# 06_-_Soft_DPHY.net
KiCad netlist of a schematic drawn in Altium Designer
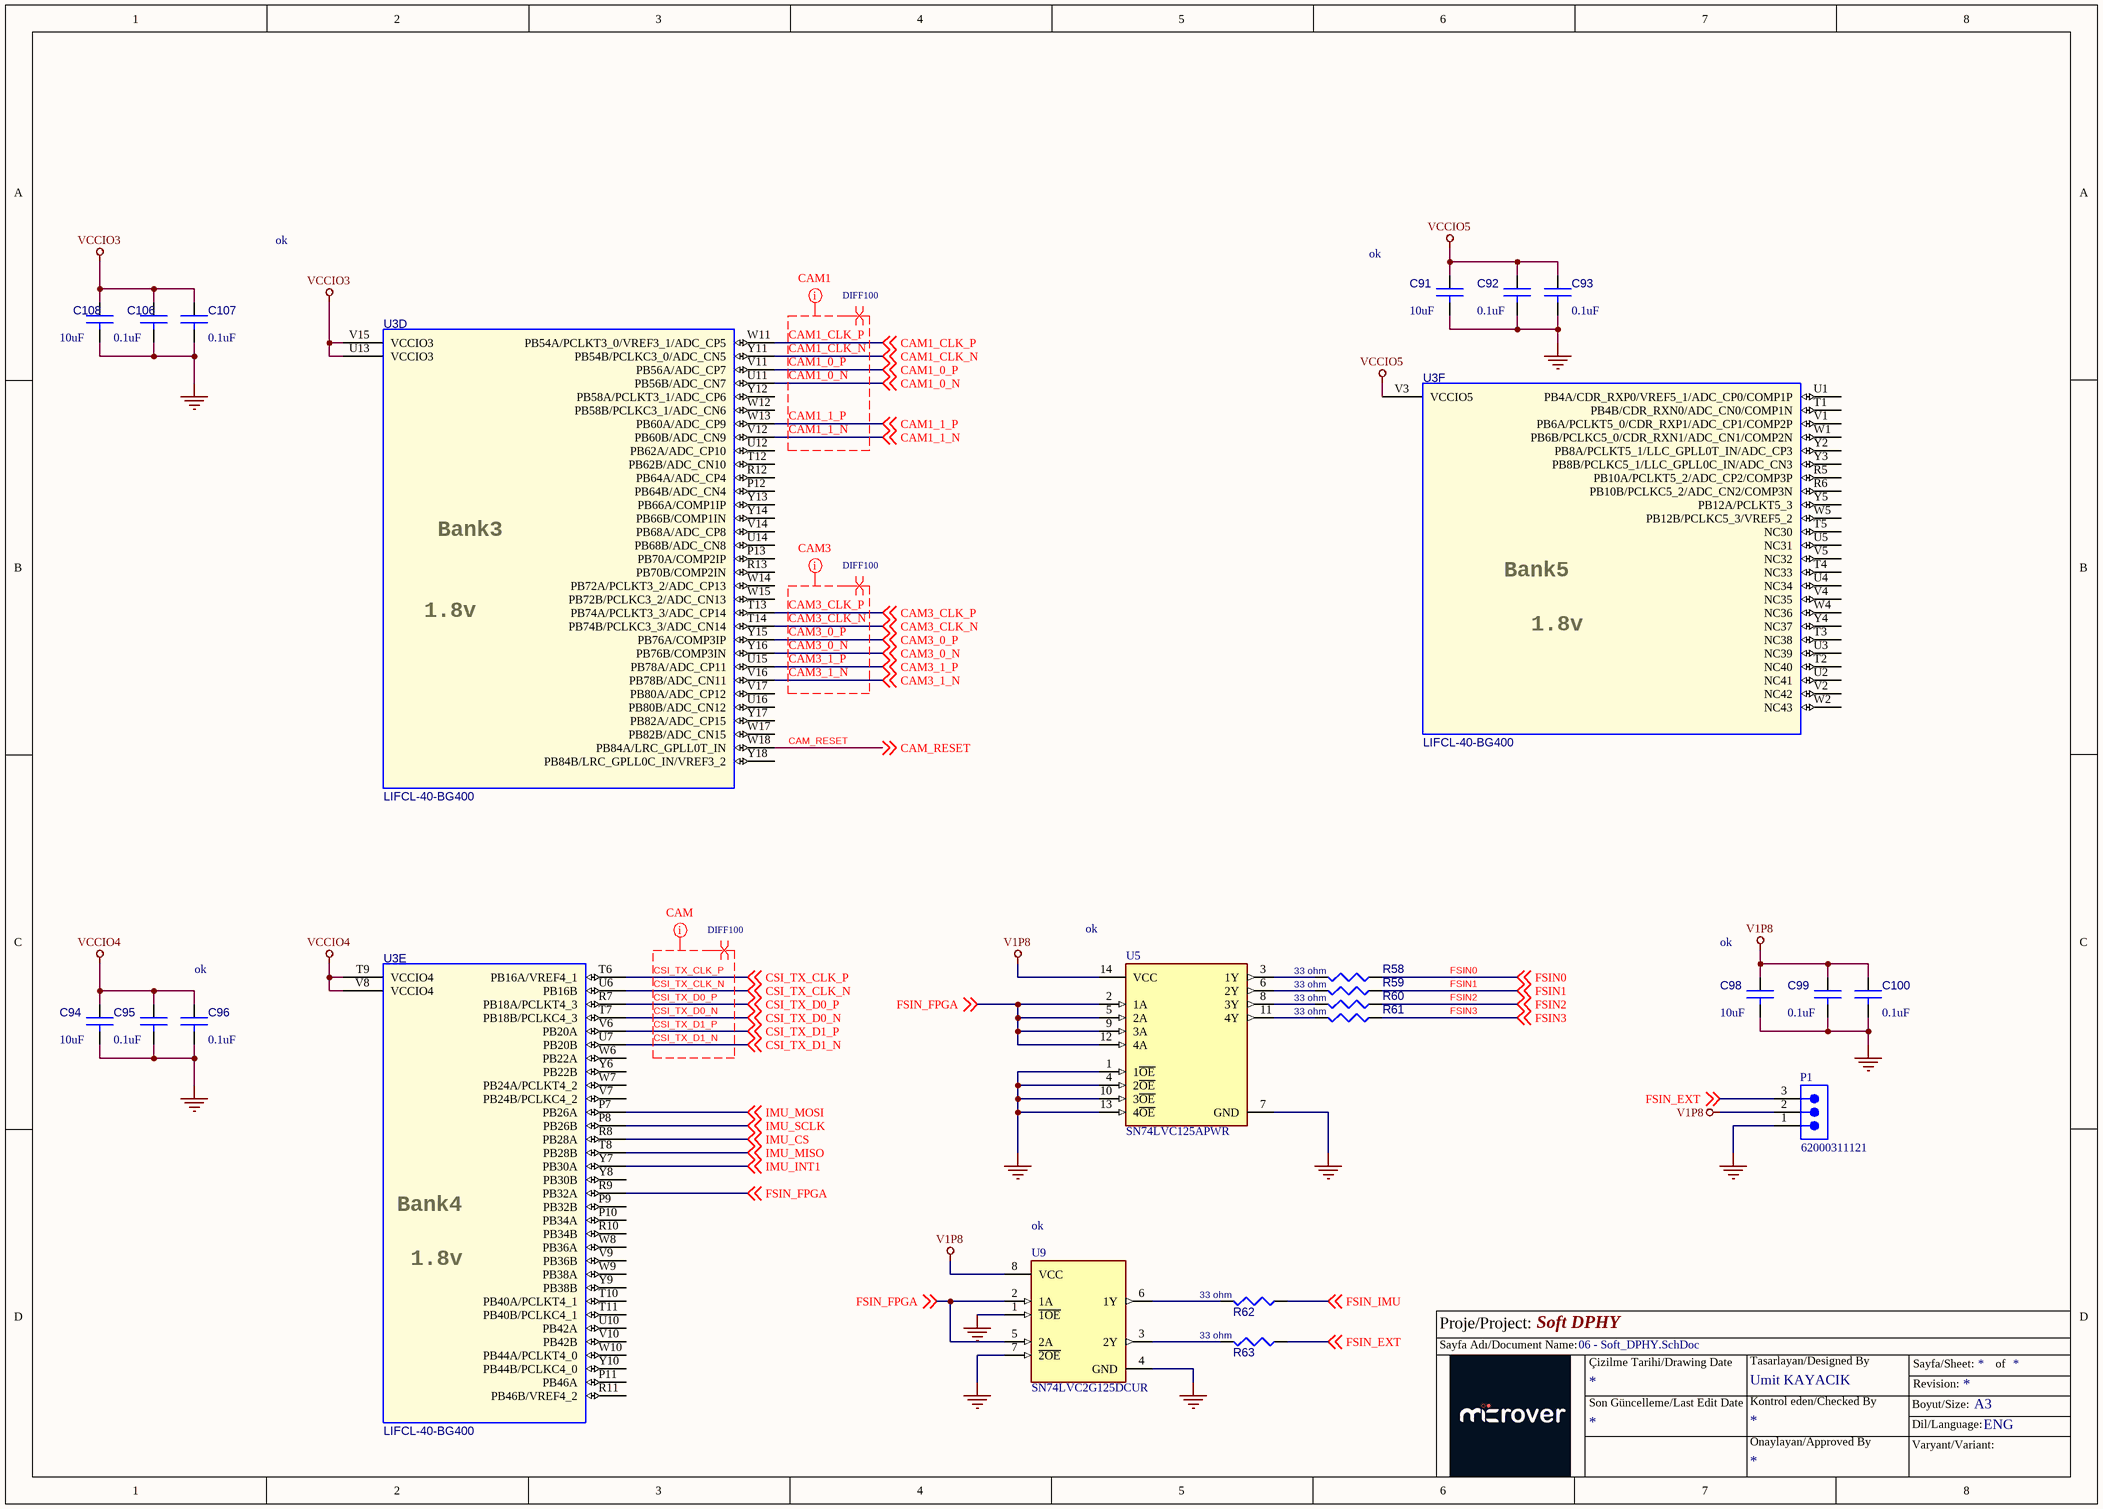
[diagram p0: 06 - Soft_DPHY.SchDoc]

(export (version "E")
  (design (tool "Eeschema 10.0.6"))
  (components
    (comp (ref "C91")
      (value "10uF")
      (footprint "C0603")
      (description "CAP CECAP CER 10UF 10V X5R 20% 0603")
      (fields
        (field (name "MANUFACTURER") "Taiyo Yuden")
        (field (name "MANUFACTURER PART NUMBER") "LMK107BJ106MALTD")
      )
      (libsource (lib "*") (part "10uF_0603"))
    )
    (comp (ref "C92")
      (value "0.1uF")
      (footprint "C0201")
      (description "CAP CER 0.1UF 25V 10% X5R 0201")
      (fields
        (field (name "MANUFACTURER") "Murata")
        (field (name "MANUFACTURER PART NUMBER") "GRM033R61E104KE14J")
      )
      (libsource (lib "*") (part "0u1_0402"))
    )
    (comp (ref "C93")
      (value "0.1uF")
      (footprint "C0201")
      (description "CAP CER 0.1UF 25V 10% X5R 0201")
      (fields
        (field (name "MANUFACTURER") "Murata")
        (field (name "MANUFACTURER PART NUMBER") "GRM033R61E104KE14J")
      )
      (libsource (lib "*") (part "0u1_0402"))
    )
    (comp (ref "C94")
      (value "10uF")
      (footprint "C0603")
      (description "CAP CECAP CER 10UF 10V X5R 20% 0603")
      (fields
        (field (name "MANUFACTURER") "Taiyo Yuden")
        (field (name "MANUFACTURER PART NUMBER") "LMK107BJ106MALTD")
      )
      (libsource (lib "*") (part "10uF_0603"))
    )
    (comp (ref "C95")
      (value "0.1uF")
      (footprint "C0201")
      (description "CAP CER 0.1UF 25V 10% X5R 0201")
      (fields
        (field (name "MANUFACTURER") "Murata")
        (field (name "MANUFACTURER PART NUMBER") "GRM033R61E104KE14J")
      )
      (libsource (lib "*") (part "0u1_0402"))
    )
    (comp (ref "C96")
      (value "0.1uF")
      (footprint "C0201")
      (description "CAP CER 0.1UF 25V 10% X5R 0201")
      (fields
        (field (name "MANUFACTURER") "Murata")
        (field (name "MANUFACTURER PART NUMBER") "GRM033R61E104KE14J")
      )
      (libsource (lib "*") (part "0u1_0402"))
    )
    (comp (ref "C98")
      (value "10uF")
      (footprint "C0603")
      (description "CAP CECAP CER 10UF 10V X5R 20% 0603")
      (fields
        (field (name "MANUFACTURER") "Taiyo Yuden")
        (field (name "MANUFACTURER PART NUMBER") "LMK107BJ106MALTD")
      )
      (libsource (lib "*") (part "10uF_0603"))
    )
    (comp (ref "C99")
      (value "0.1uF")
      (footprint "C0201")
      (description "CAP CER 0.1UF 25V 10% X5R 0201")
      (fields
        (field (name "MANUFACTURER") "Murata")
        (field (name "MANUFACTURER PART NUMBER") "GRM033R61E104KE14J")
      )
      (libsource (lib "*") (part "0u1_0402"))
    )
    (comp (ref "C100")
      (value "0.1uF")
      (footprint "C0201")
      (description "CAP CER 0.1UF 25V 10% X5R 0201")
      (fields
        (field (name "MANUFACTURER") "Murata")
        (field (name "MANUFACTURER PART NUMBER") "GRM033R61E104KE14J")
      )
      (libsource (lib "*") (part "0u1_0402"))
    )
    (comp (ref "C106")
      (value "0.1uF")
      (footprint "C0201")
      (description "CAP CER 0.1UF 25V 10% X5R 0201")
      (fields
        (field (name "MANUFACTURER") "Murata")
        (field (name "MANUFACTURER PART NUMBER") "GRM033R61E104KE14J")
      )
      (libsource (lib "*") (part "0u1_0402"))
    )
    (comp (ref "C107")
      (value "0.1uF")
      (footprint "C0201")
      (description "CAP CER 0.1UF 25V 10% X5R 0201")
      (fields
        (field (name "MANUFACTURER") "Murata")
        (field (name "MANUFACTURER PART NUMBER") "GRM033R61E104KE14J")
      )
      (libsource (lib "*") (part "0u1_0402"))
    )
    (comp (ref "C108")
      (value "10uF")
      (footprint "C0603")
      (description "CAP CECAP CER 10UF 10V X5R 20% 0603")
      (fields
        (field (name "MANUFACTURER") "Taiyo Yuden")
        (field (name "MANUFACTURER PART NUMBER") "LMK107BJ106MALTD")
      )
      (libsource (lib "*") (part "10uF_0603"))
    )
    (comp (ref "P1")
      (value "62000311121")
      (footprint "62000311121")
      (description "THT Vertical Pin Header WR-PHD, Pitch 2.00 mm, Single Row, 3 pins")
      (libsource (lib "Altium Content Vault") (part "Header_Male_1R_03P"))
    )
    (comp (ref "R58")
      (value "33 ohm")
      (footprint "R0402")
      (description "RES SMD 33 OHM 1% 1/20W 0201")
      (fields (field (name "MFG") "Yageo"))
      (libsource (lib "*") (part "RES_100K_1W16_0402_5P"))
    )
    (comp (ref "R59")
      (value "33 ohm")
      (footprint "R0402")
      (description "RES SMD 33 OHM 1% 1/20W 0201")
      (fields (field (name "MFG") "Yageo"))
      (libsource (lib "*") (part "RES_100K_1W16_0402_5P"))
    )
    (comp (ref "R60")
      (value "33 ohm")
      (footprint "R0402")
      (description "RES SMD 33 OHM 1% 1/20W 0201")
      (fields (field (name "MFG") "Yageo"))
      (libsource (lib "*") (part "RES_100K_1W16_0402_5P"))
    )
    (comp (ref "R61")
      (value "33 ohm")
      (footprint "R0402")
      (description "RES SMD 33 OHM 1% 1/20W 0201")
      (fields (field (name "MFG") "Yageo"))
      (libsource (lib "*") (part "RES_100K_1W16_0402_5P"))
    )
    (comp (ref "R62")
      (value "33 ohm")
      (footprint "RLP-100")
      (description "RES SMD 33 OHM 1% 1/20W 0201")
      (fields (field (name "MFG") "Yageo"))
      (libsource (lib "*") (part "RES_100K_1W16_0402_5P"))
    )
    (comp (ref "R63")
      (value "33 ohm")
      (footprint "R0402")
      (description "RES SMD 33 OHM 1% 1/20W 0201")
      (fields (field (name "MFG") "Yageo"))
      (libsource (lib "*") (part "RES_100K_1W16_0402_5P"))
    )
    (comp (ref "U3")
      (value "LIFCL-40-BG400")
      (footprint "LIFCL-40-BG400")
      (libsource (lib "*") (part "LIFCL-40-BG400"))
    )
    (comp (ref "U5")
      (value "SN74LVC125APWR")
      (footprint "FP-PW0014A-IPC_B")
      (description "IC BUF NON-INVERT 3.6V 14TSSOP")
      (libsource (lib "Altium Content Vault") (part "0c185306b27c65c3e4a0d950f37c68a"))
    )
    (comp (ref "U9")
      (value "SN74LVC2G125DCUR")
      (footprint "FP-DCU0008A-MFG")
      (description "IC BUFFER NON-INVERT 5.5V US8")
      (fields
        (field (name "MANUFACTURER") "Texas Instruments")
        (field (name "OCTOPART") "https://octopart.com/sn74lvc2g125dcur-texas+instruments-464564")
      )
      (libsource (lib "Altium Content Vault") (part "35a3a327bc10fafb1b5bbbc3c462791"))
    )
  )
  (nets
    (net (code "1") (name "CAM1_0_N") (class "Default")
      (node (ref "U3") (pin "U11") (pinfunction "PB56B/ADC_CN7_U11") (pintype "bidirectional"))
    )
    (net (code "2") (name "CAM1_0_P") (class "Default")
      (node (ref "U3") (pin "V11") (pinfunction "PB56A/ADC_CP7_V11") (pintype "bidirectional"))
    )
    (net (code "3") (name "CAM1_1_N") (class "Default")
      (node (ref "U3") (pin "V12") (pinfunction "PB60B/ADC_CN9_V12") (pintype "bidirectional"))
    )
    (net (code "4") (name "CAM1_1_P") (class "Default")
      (node (ref "U3") (pin "W13") (pinfunction "PB60A/ADC_CP9_W13") (pintype "bidirectional"))
    )
    (net (code "5") (name "CAM1_CLK_N") (class "Default")
      (node (ref "U3") (pin "Y11") (pinfunction "PB54B/PCLKC3_0/ADC_CN5_Y11") (pintype "bidirectional"))
    )
    (net (code "6") (name "CAM1_CLK_P") (class "Default")
      (node (ref "U3") (pin "W11") (pinfunction "PB54A/PCLKT3_0/VREF3_1/ADC_CP5_W11") (pintype "bidirectional"))
    )
    (net (code "7") (name "CAM3_0_N") (class "Default")
      (node (ref "U3") (pin "Y16") (pinfunction "PB76B/COMP3IN_Y16") (pintype "bidirectional"))
    )
    (net (code "8") (name "CAM3_0_P") (class "Default")
      (node (ref "U3") (pin "Y15") (pinfunction "PB76A/COMP3IP_Y15") (pintype "bidirectional"))
    )
    (net (code "9") (name "CAM3_1_N") (class "Default")
      (node (ref "U3") (pin "V16") (pinfunction "PB78B/ADC_CN11_V16") (pintype "bidirectional"))
    )
    (net (code "10") (name "CAM3_1_P") (class "Default")
      (node (ref "U3") (pin "U15") (pinfunction "PB78A/ADC_CP11_U15") (pintype "bidirectional"))
    )
    (net (code "11") (name "CAM3_CLK_N") (class "Default")
      (node (ref "U3") (pin "T14") (pinfunction "PB74B/PCLKC3_3/ADC_CN14_T14") (pintype "bidirectional"))
    )
    (net (code "12") (name "CAM3_CLK_P") (class "Default")
      (node (ref "U3") (pin "T13") (pinfunction "PB74A/PCLKT3_3/ADC_CP14_T13") (pintype "bidirectional"))
    )
    (net (code "13") (name "CAM_RESET") (class "Default")
      (node (ref "U3") (pin "W18") (pinfunction "PB84A/LRC_GPLL0T_IN_W18") (pintype "bidirectional"))
    )
    (net (code "14") (name "CSI_TX_CLK_N") (class "Default")
      (node (ref "U3") (pin "U6") (pinfunction "PB16B_U6") (pintype "bidirectional"))
    )
    (net (code "15") (name "CSI_TX_CLK_P") (class "Default")
      (node (ref "U3") (pin "T6") (pinfunction "PB16A/VREF4_1_T6") (pintype "bidirectional"))
    )
    (net (code "16") (name "CSI_TX_D0_N") (class "Default")
      (node (ref "U3") (pin "T7") (pinfunction "PB18B/PCLKC4_3_T7") (pintype "bidirectional"))
    )
    (net (code "17") (name "CSI_TX_D0_P") (class "Default")
      (node (ref "U3") (pin "R7") (pinfunction "PB18A/PCLKT4_3_R7") (pintype "bidirectional"))
    )
    (net (code "18") (name "CSI_TX_D1_N") (class "Default")
      (node (ref "U3") (pin "U7") (pinfunction "PB20B_U7") (pintype "bidirectional"))
    )
    (net (code "19") (name "CSI_TX_D1_P") (class "Default")
      (node (ref "U3") (pin "V6") (pinfunction "PB20A_V6") (pintype "bidirectional"))
    )
    (net (code "20") (name "FSIN0") (class "Default")
      (node (ref "R58") (pin "2") (pinfunction "2_2") (pintype "passive"))
    )
    (net (code "21") (name "FSIN1") (class "Default")
      (node (ref "R59") (pin "2") (pinfunction "2_2") (pintype "passive"))
    )
    (net (code "22") (name "FSIN2") (class "Default")
      (node (ref "R60") (pin "2") (pinfunction "2_2") (pintype "passive"))
    )
    (net (code "23") (name "FSIN3") (class "Default")
      (node (ref "R61") (pin "2") (pinfunction "2_2") (pintype "passive"))
    )
    (net (code "24") (name "FSIN_EXT") (class "Default")
      (node (ref "P1") (pin "3") (pinfunction "3_3") (pintype "passive"))
      (node (ref "R63") (pin "2") (pinfunction "2_2") (pintype "passive"))
    )
    (net (code "25") (name "FSIN_FPGA") (class "Default")
      (node (ref "U3") (pin "R9") (pinfunction "PB32A_R9") (pintype "bidirectional"))
      (node (ref "U5") (pin "12") (pinfunction "4A_12") (pintype "input"))
      (node (ref "U5") (pin "2") (pinfunction "1A_2") (pintype "input"))
      (node (ref "U5") (pin "5") (pinfunction "2A_5") (pintype "input"))
      (node (ref "U5") (pin "9") (pinfunction "3A_9") (pintype "input"))
      (node (ref "U9") (pin "2") (pinfunction "1A_2") (pintype "input"))
      (node (ref "U9") (pin "5") (pinfunction "2A_5") (pintype "input"))
    )
    (net (code "26") (name "FSIN_IMU") (class "Default")
      (node (ref "R62") (pin "2") (pinfunction "2_2") (pintype "passive"))
    )
    (net (code "27") (name "GND") (class "Default")
      (node (ref "C100") (pin "2") (pinfunction "2_2") (pintype "passive"))
      (node (ref "C106") (pin "2") (pinfunction "2_2") (pintype "passive"))
      (node (ref "C107") (pin "2") (pinfunction "2_2") (pintype "passive"))
      (node (ref "C108") (pin "2") (pinfunction "2_2") (pintype "passive"))
      (node (ref "C91") (pin "2") (pinfunction "2_2") (pintype "passive"))
      (node (ref "C92") (pin "2") (pinfunction "2_2") (pintype "passive"))
      (node (ref "C93") (pin "2") (pinfunction "2_2") (pintype "passive"))
      (node (ref "C94") (pin "2") (pinfunction "2_2") (pintype "passive"))
      (node (ref "C95") (pin "2") (pinfunction "2_2") (pintype "passive"))
      (node (ref "C96") (pin "2") (pinfunction "2_2") (pintype "passive"))
      (node (ref "C98") (pin "2") (pinfunction "2_2") (pintype "passive"))
      (node (ref "C99") (pin "2") (pinfunction "2_2") (pintype "passive"))
      (node (ref "P1") (pin "1") (pinfunction "1_1") (pintype "passive"))
      (node (ref "U5") (pin "1") (pinfunction "1~{OE}_1") (pintype "input"))
      (node (ref "U5") (pin "10") (pinfunction "3~{OE}_10") (pintype "input"))
      (node (ref "U5") (pin "13") (pinfunction "4~{OE}_13") (pintype "input"))
      (node (ref "U5") (pin "4") (pinfunction "2~{OE}_4") (pintype "input"))
      (node (ref "U5") (pin "7") (pinfunction "GND_7") (pintype "power_in"))
      (node (ref "U9") (pin "1") (pinfunction "~{1OE}_1") (pintype "input"))
      (node (ref "U9") (pin "4") (pinfunction "GND_4") (pintype "power_in"))
      (node (ref "U9") (pin "7") (pinfunction "~{2OE}_7") (pintype "input"))
    )
    (net (code "28") (name "IMU_CS") (class "Default")
      (node (ref "U3") (pin "R8") (pinfunction "PB28A_R8") (pintype "bidirectional"))
    )
    (net (code "29") (name "IMU_INT1") (class "Default")
      (node (ref "U3") (pin "Y7") (pinfunction "PB30A_Y7") (pintype "bidirectional"))
    )
    (net (code "30") (name "IMU_MISO") (class "Default")
      (node (ref "U3") (pin "T8") (pinfunction "PB28B_T8") (pintype "bidirectional"))
    )
    (net (code "31") (name "IMU_MOSI") (class "Default")
      (node (ref "U3") (pin "P7") (pinfunction "PB26A_P7") (pintype "bidirectional"))
    )
    (net (code "32") (name "IMU_SCLK") (class "Default")
      (node (ref "U3") (pin "P8") (pinfunction "PB26B_P8") (pintype "bidirectional"))
    )
    (net (code "33") (name "Net-(U5-1Y)") (class "Default")
      (node (ref "R58") (pin "1") (pinfunction "1_1") (pintype "passive"))
      (node (ref "U5") (pin "3") (pinfunction "1Y_3") (pintype "output"))
    )
    (net (code "34") (name "Net-(U5-2Y)") (class "Default")
      (node (ref "R59") (pin "1") (pinfunction "1_1") (pintype "passive"))
      (node (ref "U5") (pin "6") (pinfunction "2Y_6") (pintype "output"))
    )
    (net (code "35") (name "Net-(U5-3Y)") (class "Default")
      (node (ref "R60") (pin "1") (pinfunction "1_1") (pintype "passive"))
      (node (ref "U5") (pin "8") (pinfunction "3Y_8") (pintype "output"))
    )
    (net (code "36") (name "Net-(U5-4Y)") (class "Default")
      (node (ref "R61") (pin "1") (pinfunction "1_1") (pintype "passive"))
      (node (ref "U5") (pin "11") (pinfunction "4Y_11") (pintype "output"))
    )
    (net (code "37") (name "Net-(U9-1Y)") (class "Default")
      (node (ref "R62") (pin "1") (pinfunction "1_1") (pintype "passive"))
      (node (ref "U9") (pin "6") (pinfunction "1Y_6") (pintype "output"))
    )
    (net (code "38") (name "Net-(U9-2Y)") (class "Default")
      (node (ref "R63") (pin "1") (pinfunction "1_1") (pintype "passive"))
      (node (ref "U9") (pin "3") (pinfunction "2Y_3") (pintype "output"))
    )
    (net (code "39") (name "V1P8") (class "Default")
      (node (ref "C100") (pin "1") (pinfunction "1_1") (pintype "passive"))
      (node (ref "C98") (pin "1") (pinfunction "1_1") (pintype "passive"))
      (node (ref "C99") (pin "1") (pinfunction "1_1") (pintype "passive"))
      (node (ref "P1") (pin "2") (pinfunction "2_2") (pintype "passive"))
      (node (ref "U5") (pin "14") (pinfunction "VCC_14") (pintype "power_in"))
      (node (ref "U9") (pin "8") (pinfunction "VCC_8") (pintype "power_in"))
    )
    (net (code "40") (name "VCCIO3") (class "Default")
      (node (ref "C106") (pin "1") (pinfunction "1_1") (pintype "passive"))
      (node (ref "C107") (pin "1") (pinfunction "1_1") (pintype "passive"))
      (node (ref "C108") (pin "1") (pinfunction "1_1") (pintype "passive"))
      (node (ref "U3") (pin "U13") (pinfunction "VCCIO3_U13") (pintype "power_in"))
      (node (ref "U3") (pin "V15") (pinfunction "VCCIO3_V15") (pintype "power_in"))
    )
    (net (code "41") (name "VCCIO4") (class "Default")
      (node (ref "C94") (pin "1") (pinfunction "1_1") (pintype "passive"))
      (node (ref "C95") (pin "1") (pinfunction "1_1") (pintype "passive"))
      (node (ref "C96") (pin "1") (pinfunction "1_1") (pintype "passive"))
      (node (ref "U3") (pin "T9") (pinfunction "VCCIO4_T9") (pintype "power_in"))
      (node (ref "U3") (pin "V8") (pinfunction "VCCIO4_V8") (pintype "power_in"))
    )
    (net (code "42") (name "VCCIO5") (class "Default")
      (node (ref "C91") (pin "1") (pinfunction "1_1") (pintype "passive"))
      (node (ref "C92") (pin "1") (pinfunction "1_1") (pintype "passive"))
      (node (ref "C93") (pin "1") (pinfunction "1_1") (pintype "passive"))
      (node (ref "U3") (pin "V3") (pinfunction "VCCIO5_V3") (pintype "power_in"))
    )
    (net (code "43") (name "unconnected-(U3D-PB58A{slash}PCLKT3_1{slash}ADC_CP6-PadY12)") (class "Default")
      (node (ref "U3") (pin "Y12") (pinfunction "PB58A/PCLKT3_1/ADC_CP6_Y12") (pintype "bidirectional"))
    )
    (net (code "44") (name "unconnected-(U3D-PB58B{slash}PCLKC3_1{slash}ADC_CN6-PadW12)") (class "Default")
      (node (ref "U3") (pin "W12") (pinfunction "PB58B/PCLKC3_1/ADC_CN6_W12") (pintype "bidirectional"))
    )
    (net (code "45") (name "unconnected-(U3D-PB62A{slash}ADC_CP10-PadU12)") (class "Default")
      (node (ref "U3") (pin "U12") (pinfunction "PB62A/ADC_CP10_U12") (pintype "bidirectional"))
    )
    (net (code "46") (name "unconnected-(U3D-PB62B{slash}ADC_CN10-PadT12)") (class "Default")
      (node (ref "U3") (pin "T12") (pinfunction "PB62B/ADC_CN10_T12") (pintype "bidirectional"))
    )
    (net (code "47") (name "unconnected-(U3D-PB64A{slash}ADC_CP4-PadR12)") (class "Default")
      (node (ref "U3") (pin "R12") (pinfunction "PB64A/ADC_CP4_R12") (pintype "bidirectional"))
    )
    (net (code "48") (name "unconnected-(U3D-PB64B{slash}ADC_CN4-PadP12)") (class "Default")
      (node (ref "U3") (pin "P12") (pinfunction "PB64B/ADC_CN4_P12") (pintype "bidirectional"))
    )
    (net (code "49") (name "unconnected-(U3D-PB66A{slash}COMP1IP-PadY13)") (class "Default")
      (node (ref "U3") (pin "Y13") (pinfunction "PB66A/COMP1IP_Y13") (pintype "bidirectional"))
    )
    (net (code "50") (name "unconnected-(U3D-PB66B{slash}COMP1IN-PadY14)") (class "Default")
      (node (ref "U3") (pin "Y14") (pinfunction "PB66B/COMP1IN_Y14") (pintype "bidirectional"))
    )
    (net (code "51") (name "unconnected-(U3D-PB68A{slash}ADC_CP8-PadV14)") (class "Default")
      (node (ref "U3") (pin "V14") (pinfunction "PB68A/ADC_CP8_V14") (pintype "bidirectional"))
    )
    (net (code "52") (name "unconnected-(U3D-PB68B{slash}ADC_CN8-PadU14)") (class "Default")
      (node (ref "U3") (pin "U14") (pinfunction "PB68B/ADC_CN8_U14") (pintype "bidirectional"))
    )
    (net (code "53") (name "unconnected-(U3D-PB70A{slash}COMP2IP-PadP13)") (class "Default")
      (node (ref "U3") (pin "P13") (pinfunction "PB70A/COMP2IP_P13") (pintype "bidirectional"))
    )
    (net (code "54") (name "unconnected-(U3D-PB70B{slash}COMP2IN-PadR13)") (class "Default")
      (node (ref "U3") (pin "R13") (pinfunction "PB70B/COMP2IN_R13") (pintype "bidirectional"))
    )
    (net (code "55") (name "unconnected-(U3D-PB72A{slash}PCLKT3_2{slash}ADC_CP13-PadW14)") (class "Default")
      (node (ref "U3") (pin "W14") (pinfunction "PB72A/PCLKT3_2/ADC_CP13_W14") (pintype "bidirectional"))
    )
    (net (code "56") (name "unconnected-(U3D-PB72B{slash}PCLKC3_2{slash}ADC_CN13-PadW15)") (class "Default")
      (node (ref "U3") (pin "W15") (pinfunction "PB72B/PCLKC3_2/ADC_CN13_W15") (pintype "bidirectional"))
    )
    (net (code "57") (name "unconnected-(U3D-PB80A{slash}ADC_CP12-PadV17)") (class "Default")
      (node (ref "U3") (pin "V17") (pinfunction "PB80A/ADC_CP12_V17") (pintype "bidirectional"))
    )
    (net (code "58") (name "unconnected-(U3D-PB80B{slash}ADC_CN12-PadU16)") (class "Default")
      (node (ref "U3") (pin "U16") (pinfunction "PB80B/ADC_CN12_U16") (pintype "bidirectional"))
    )
    (net (code "59") (name "unconnected-(U3D-PB82A{slash}ADC_CP15-PadY17)") (class "Default")
      (node (ref "U3") (pin "Y17") (pinfunction "PB82A/ADC_CP15_Y17") (pintype "bidirectional"))
    )
    (net (code "60") (name "unconnected-(U3D-PB82B{slash}ADC_CN15-PadW17)") (class "Default")
      (node (ref "U3") (pin "W17") (pinfunction "PB82B/ADC_CN15_W17") (pintype "bidirectional"))
    )
    (net (code "61") (name "unconnected-(U3D-PB84B{slash}LRC_GPLL0C_IN{slash}VREF3_2-PadY18)") (class "Default")
      (node (ref "U3") (pin "Y18") (pinfunction "PB84B/LRC_GPLL0C_IN/VREF3_2_Y18") (pintype "bidirectional"))
    )
    (net (code "62") (name "unconnected-(U3E-PB22A-PadW6)") (class "Default")
      (node (ref "U3") (pin "W6") (pinfunction "PB22A_W6") (pintype "bidirectional"))
    )
    (net (code "63") (name "unconnected-(U3E-PB22B-PadY6)") (class "Default")
      (node (ref "U3") (pin "Y6") (pinfunction "PB22B_Y6") (pintype "bidirectional"))
    )
    (net (code "64") (name "unconnected-(U3E-PB24A{slash}PCLKT4_2-PadW7)") (class "Default")
      (node (ref "U3") (pin "W7") (pinfunction "PB24A/PCLKT4_2_W7") (pintype "bidirectional"))
    )
    (net (code "65") (name "unconnected-(U3E-PB24B{slash}PCLKC4_2-PadV7)") (class "Default")
      (node (ref "U3") (pin "V7") (pinfunction "PB24B/PCLKC4_2_V7") (pintype "bidirectional"))
    )
    (net (code "66") (name "unconnected-(U3E-PB30B-PadY8)") (class "Default")
      (node (ref "U3") (pin "Y8") (pinfunction "PB30B_Y8") (pintype "bidirectional"))
    )
    (net (code "67") (name "unconnected-(U3E-PB32B-PadP9)") (class "Default")
      (node (ref "U3") (pin "P9") (pinfunction "PB32B_P9") (pintype "bidirectional"))
    )
    (net (code "68") (name "unconnected-(U3E-PB34A-PadP10)") (class "Default")
      (node (ref "U3") (pin "P10") (pinfunction "PB34A_P10") (pintype "bidirectional"))
    )
    (net (code "69") (name "unconnected-(U3E-PB34B-PadR10)") (class "Default")
      (node (ref "U3") (pin "R10") (pinfunction "PB34B_R10") (pintype "bidirectional"))
    )
    (net (code "70") (name "unconnected-(U3E-PB36A-PadW8)") (class "Default")
      (node (ref "U3") (pin "W8") (pinfunction "PB36A_W8") (pintype "bidirectional"))
    )
    (net (code "71") (name "unconnected-(U3E-PB36B-PadV9)") (class "Default")
      (node (ref "U3") (pin "V9") (pinfunction "PB36B_V9") (pintype "bidirectional"))
    )
    (net (code "72") (name "unconnected-(U3E-PB38A-PadW9)") (class "Default")
      (node (ref "U3") (pin "W9") (pinfunction "PB38A_W9") (pintype "bidirectional"))
    )
    (net (code "73") (name "unconnected-(U3E-PB38B-PadY9)") (class "Default")
      (node (ref "U3") (pin "Y9") (pinfunction "PB38B_Y9") (pintype "bidirectional"))
    )
    (net (code "74") (name "unconnected-(U3E-PB40A{slash}PCLKT4_1-PadT10)") (class "Default")
      (node (ref "U3") (pin "T10") (pinfunction "PB40A/PCLKT4_1_T10") (pintype "bidirectional"))
    )
    (net (code "75") (name "unconnected-(U3E-PB40B{slash}PCLKC4_1-PadT11)") (class "Default")
      (node (ref "U3") (pin "T11") (pinfunction "PB40B/PCLKC4_1_T11") (pintype "bidirectional"))
    )
    (net (code "76") (name "unconnected-(U3E-PB42A-PadU10)") (class "Default")
      (node (ref "U3") (pin "U10") (pinfunction "PB42A_U10") (pintype "bidirectional"))
    )
    (net (code "77") (name "unconnected-(U3E-PB42B-PadV10)") (class "Default")
      (node (ref "U3") (pin "V10") (pinfunction "PB42B_V10") (pintype "bidirectional"))
    )
    (net (code "78") (name "unconnected-(U3E-PB44A{slash}PCLKT4_0-PadW10)") (class "Default")
      (node (ref "U3") (pin "W10") (pinfunction "PB44A/PCLKT4_0_W10") (pintype "bidirectional"))
    )
    (net (code "79") (name "unconnected-(U3E-PB44B{slash}PCLKC4_0-PadY10)") (class "Default")
      (node (ref "U3") (pin "Y10") (pinfunction "PB44B/PCLKC4_0_Y10") (pintype "bidirectional"))
    )
    (net (code "80") (name "unconnected-(U3E-PB46A-PadP11)") (class "Default")
      (node (ref "U3") (pin "P11") (pinfunction "PB46A_P11") (pintype "bidirectional"))
    )
    (net (code "81") (name "unconnected-(U3E-PB46B{slash}VREF4_2-PadR11)") (class "Default")
      (node (ref "U3") (pin "R11") (pinfunction "PB46B/VREF4_2_R11") (pintype "bidirectional"))
    )
    (net (code "82") (name "unconnected-(U3F-NC30-PadT5)") (class "Default")
      (node (ref "U3") (pin "T5") (pinfunction "NC30_T5") (pintype "bidirectional"))
    )
    (net (code "83") (name "unconnected-(U3F-NC31-PadU5)") (class "Default")
      (node (ref "U3") (pin "U5") (pinfunction "NC31_U5") (pintype "bidirectional"))
    )
    (net (code "84") (name "unconnected-(U3F-NC32-PadV5)") (class "Default")
      (node (ref "U3") (pin "V5") (pinfunction "NC32_V5") (pintype "bidirectional"))
    )
    (net (code "85") (name "unconnected-(U3F-NC33-PadT4)") (class "Default")
      (node (ref "U3") (pin "T4") (pinfunction "NC33_T4") (pintype "bidirectional"))
    )
    (net (code "86") (name "unconnected-(U3F-NC34-PadU4)") (class "Default")
      (node (ref "U3") (pin "U4") (pinfunction "NC34_U4") (pintype "bidirectional"))
    )
    (net (code "87") (name "unconnected-(U3F-NC35-PadV4)") (class "Default")
      (node (ref "U3") (pin "V4") (pinfunction "NC35_V4") (pintype "bidirectional"))
    )
    (net (code "88") (name "unconnected-(U3F-NC36-PadW4)") (class "Default")
      (node (ref "U3") (pin "W4") (pinfunction "NC36_W4") (pintype "bidirectional"))
    )
    (net (code "89") (name "unconnected-(U3F-NC37-PadY4)") (class "Default")
      (node (ref "U3") (pin "Y4") (pinfunction "NC37_Y4") (pintype "bidirectional"))
    )
    (net (code "90") (name "unconnected-(U3F-NC38-PadT3)") (class "Default")
      (node (ref "U3") (pin "T3") (pinfunction "NC38_T3") (pintype "bidirectional"))
    )
    (net (code "91") (name "unconnected-(U3F-NC39-PadU3)") (class "Default")
      (node (ref "U3") (pin "U3") (pinfunction "NC39_U3") (pintype "bidirectional"))
    )
    (net (code "92") (name "unconnected-(U3F-NC40-PadT2)") (class "Default")
      (node (ref "U3") (pin "T2") (pinfunction "NC40_T2") (pintype "bidirectional"))
    )
    (net (code "93") (name "unconnected-(U3F-NC41-PadU2)") (class "Default")
      (node (ref "U3") (pin "U2") (pinfunction "NC41_U2") (pintype "bidirectional"))
    )
    (net (code "94") (name "unconnected-(U3F-NC42-PadV2)") (class "Default")
      (node (ref "U3") (pin "V2") (pinfunction "NC42_V2") (pintype "bidirectional"))
    )
    (net (code "95") (name "unconnected-(U3F-NC43-PadW2)") (class "Default")
      (node (ref "U3") (pin "W2") (pinfunction "NC43_W2") (pintype "bidirectional"))
    )
    (net (code "96") (name "unconnected-(U3F-PB4A{slash}CDR_RXP0{slash}VREF5_1{slash}ADC_CP0{slash}COMP1P-PadU1)") (class "Default")
      (node (ref "U3") (pin "U1") (pinfunction "PB4A/CDR_RXP0/VREF5_1/ADC_CP0/COMP1P_U1") (pintype "bidirectional"))
    )
    (net (code "97") (name "unconnected-(U3F-PB4B{slash}CDR_RXN0{slash}ADC_CN0{slash}COMP1N-PadT1)") (class "Default")
      (node (ref "U3") (pin "T1") (pinfunction "PB4B/CDR_RXN0/ADC_CN0/COMP1N_T1") (pintype "bidirectional"))
    )
    (net (code "98") (name "unconnected-(U3F-PB6A{slash}PCLKT5_0{slash}CDR_RXP1{slash}ADC_CP1{slash}COMP2P-PadV1)") (class "Default")
      (node (ref "U3") (pin "V1") (pinfunction "PB6A/PCLKT5_0/CDR_RXP1/ADC_CP1/COMP2P_V1") (pintype "bidirectional"))
    )
    (net (code "99") (name "unconnected-(U3F-PB6B{slash}PCLKC5_0{slash}CDR_RXN1{slash}ADC_CN1{slash}COMP2N-PadW1)") (class "Default")
      (node (ref "U3") (pin "W1") (pinfunction "PB6B/PCLKC5_0/CDR_RXN1/ADC_CN1/COMP2N_W1") (pintype "bidirectional"))
    )
    (net (code "100") (name "unconnected-(U3F-PB8A{slash}PCLKT5_1{slash}LLC_GPLL0T_IN{slash}ADC_CP3-PadY2)") (class "Default")
      (node (ref "U3") (pin "Y2") (pinfunction "PB8A/PCLKT5_1/LLC_GPLL0T_IN/ADC_CP3_Y2") (pintype "bidirectional"))
    )
    (net (code "101") (name "unconnected-(U3F-PB8B{slash}PCLKC5_1{slash}LLC_GPLL0C_IN{slash}ADC_CN3-PadY3)") (class "Default")
      (node (ref "U3") (pin "Y3") (pinfunction "PB8B/PCLKC5_1/LLC_GPLL0C_IN/ADC_CN3_Y3") (pintype "bidirectional"))
    )
    (net (code "102") (name "unconnected-(U3F-PB10A{slash}PCLKT5_2{slash}ADC_CP2{slash}COMP3P-PadR5)") (class "Default")
      (node (ref "U3") (pin "R5") (pinfunction "PB10A/PCLKT5_2/ADC_CP2/COMP3P_R5") (pintype "bidirectional"))
    )
    (net (code "103") (name "unconnected-(U3F-PB10B{slash}PCLKC5_2{slash}ADC_CN2{slash}COMP3N-PadR6)") (class "Default")
      (node (ref "U3") (pin "R6") (pinfunction "PB10B/PCLKC5_2/ADC_CN2/COMP3N_R6") (pintype "bidirectional"))
    )
    (net (code "104") (name "unconnected-(U3F-PB12A{slash}PCLKT5_3-PadY5)") (class "Default")
      (node (ref "U3") (pin "Y5") (pinfunction "PB12A/PCLKT5_3_Y5") (pintype "bidirectional"))
    )
    (net (code "105") (name "unconnected-(U3F-PB12B{slash}PCLKC5_3{slash}VREF5_2-PadW5)") (class "Default")
      (node (ref "U3") (pin "W5") (pinfunction "PB12B/PCLKC5_3/VREF5_2_W5") (pintype "bidirectional"))
    )
  )
)
